# AQ-sensors-Hardware-design.net
KiCad netlist of a schematic drawn in EAGLE
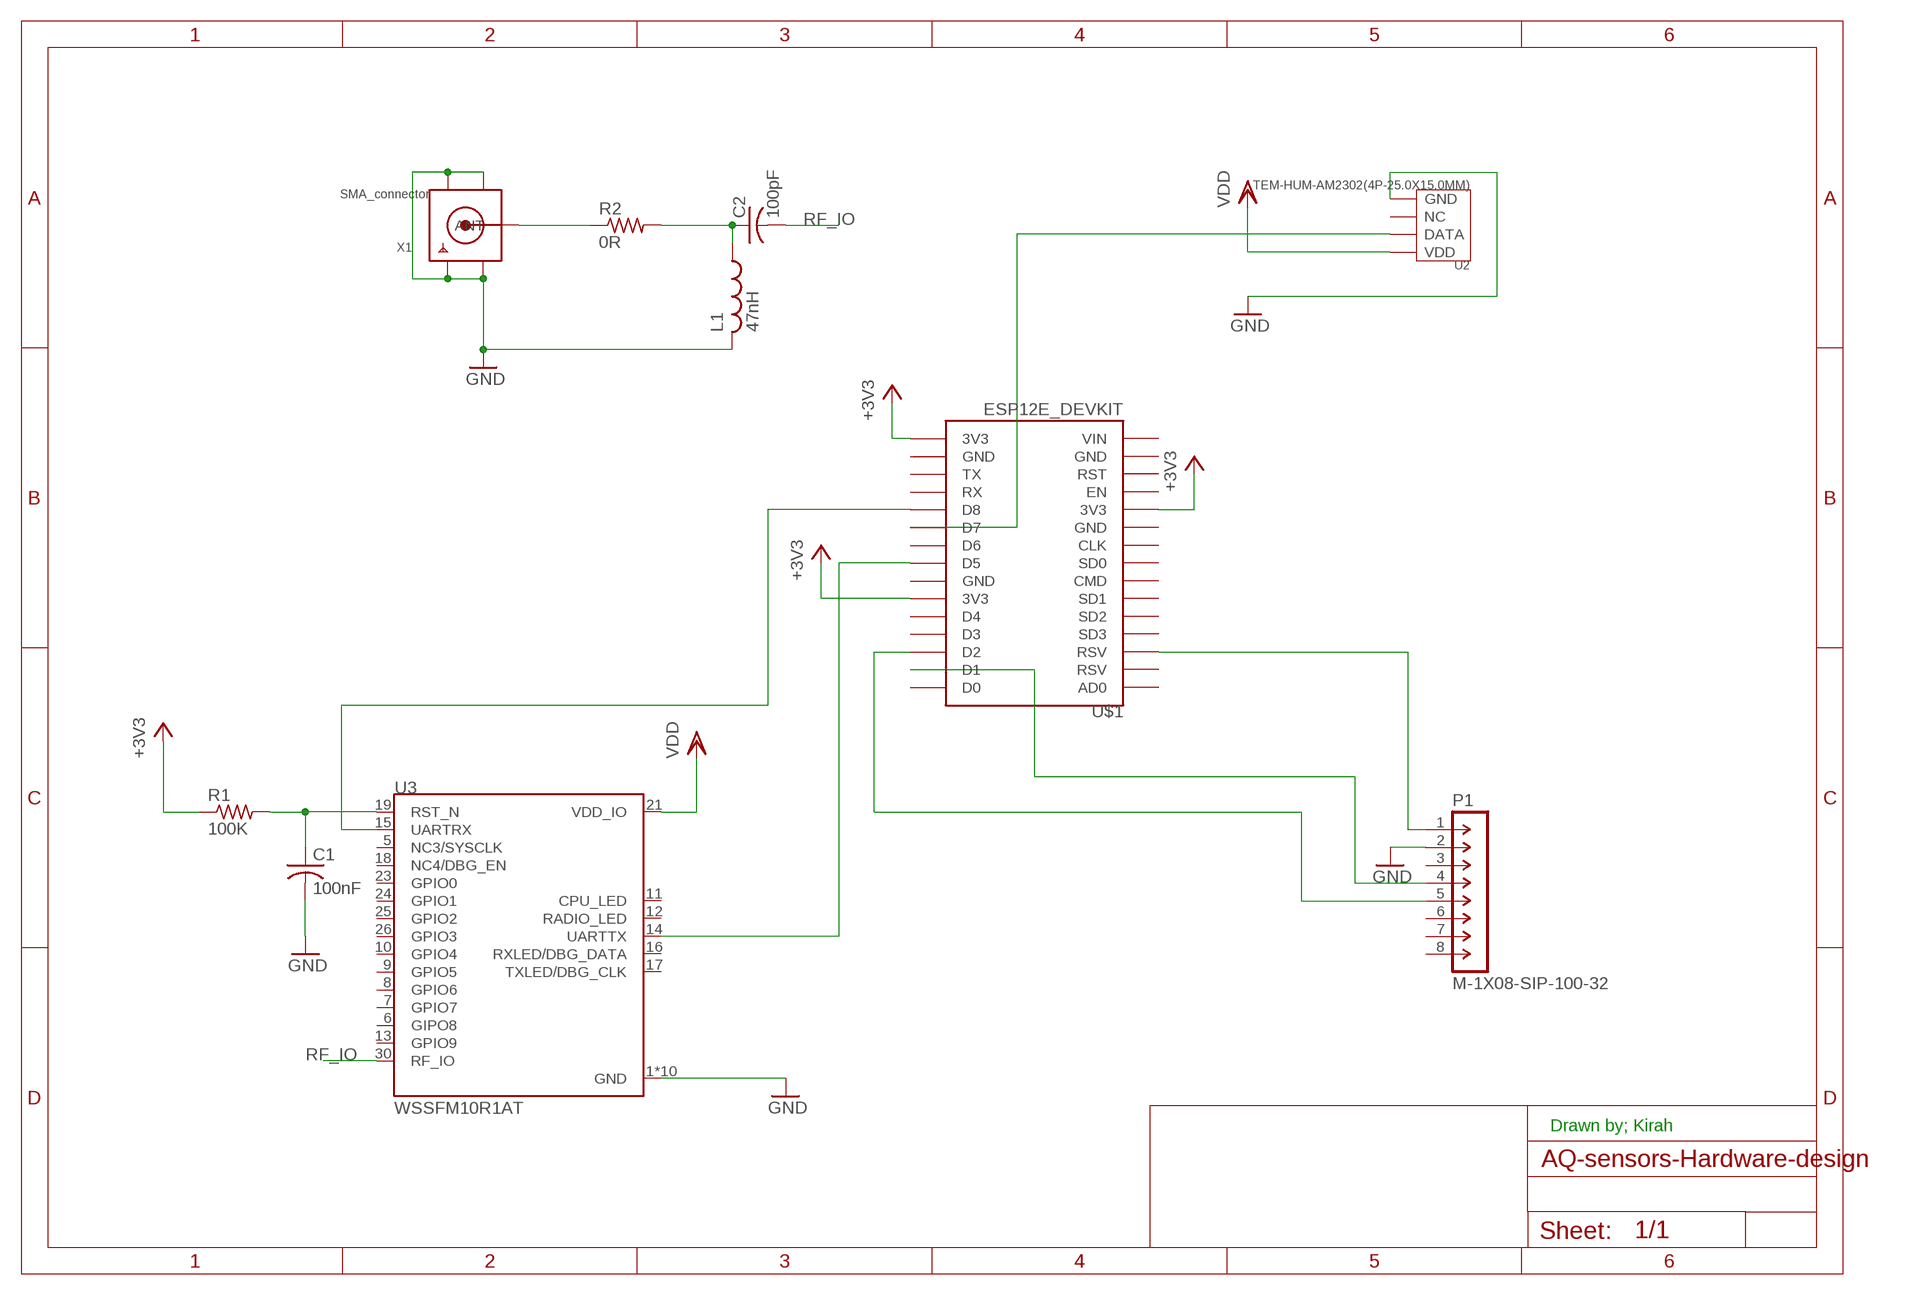
[diagram p0: schematic, sheet 1]

(export (version "E")
  (design (tool "Eeschema 10.0.6"))
  (components
    (comp (ref "C1")
      (value "100nF")
      (footprint "eagle-import:C025-025X050")
      (libsource (lib "eagle-import") (part "C-US025-025X050"))
    )
    (comp (ref "C2")
      (value "100pF")
      (footprint "eagle-import:C025-025X050")
      (libsource (lib "eagle-import") (part "C-US025-025X050"))
    )
    (comp (ref "L1")
      (value "47nH")
      (footprint "eagle-import:0204_7")
      (libsource (lib "eagle-import") (part "L-US0204/7"))
    )
    (comp (ref "P1")
      (value "M-1X08-SIP-100-32")
      (footprint "eagle-import:SIP-100-08-32")
      (libsource (lib "eagle-import") (part "M-1X08-SIP-100-32"))
    )
    (comp (ref "R1")
      (value "100K")
      (footprint "eagle-import:0204_7")
      (libsource (lib "eagle-import") (part "R-US_0204/7"))
    )
    (comp (ref "R2")
      (value "0R")
      (footprint "eagle-import:0204_7")
      (libsource (lib "eagle-import") (part "R-US_0204/7"))
    )
    (comp (ref "U$1")
      (value "ESP12E_DEVKIT")
      (footprint "eagle-import:ESP12E_DEVKIT")
      (libsource (lib "eagle-import") (part "ESP12E_DEVKIT"))
    )
    (comp (ref "U2")
      (value "TEM-HUM-AM2302(4P-25.0X15.0MM)")
      (footprint "eagle-import:SNR4-2.54-25.0X15.0X7.0MM")
      (fields (field (name "MF") "MCM Electronics") (field (name "MP") "AM2302"))
      (libsource (lib "eagle-import") (part "TEM-HUM-AM2302(4P-25.0X15.0MM)"))
    )
    (comp (ref "U3")
      (value "WSSFM10R1AT")
      (footprint "eagle-import:XCVR_WSSFM10R1AT")
      (fields (field (name "MF") "Avnet Design Services"))
      (libsource (lib "eagle-import") (part "WSSFM10R1AT"))
    )
    (comp (ref "X1")
      (value "SMA_connector")
      (footprint "eagle-import:SMA_EDGELAUNCH_UFL")
      (libsource (lib "eagle-import") (part "SMACONNECTOR_EDGE_UFL"))
    )
  )
  (nets
    (net (code "1") (name "+3V3") (class "Default")
      (node (ref "R1") (pin "1") (pinfunction "1_1") (pintype "passive"))
      (node (ref "U$1") (pin "3V3@0") (pinfunction "3V3_3V3@0") (pintype "bidirectional"))
      (node (ref "U$1") (pin "3V3@1") (pinfunction "3V3_3V3@1") (pintype "bidirectional"))
      (node (ref "U$1") (pin "3V3@2") (pinfunction "3V3_3V3@2") (pintype "bidirectional"))
    )
    (net (code "2") (name "/RF_IO") (class "Default")
      (node (ref "C2") (pin "2") (pinfunction "2_2") (pintype "passive"))
      (node (ref "U3") (pin "30") (pinfunction "RF_IO_30") (pintype "bidirectional"))
    )
    (net (code "3") (name "GND") (class "Default")
      (node (ref "C1") (pin "2") (pinfunction "2_2") (pintype "passive"))
      (node (ref "L1") (pin "2") (pinfunction "2_2") (pintype "passive"))
      (node (ref "P1") (pin "2") (pinfunction "2_2") (pintype "passive"))
      (node (ref "U2") (pin "P$4") (pinfunction "GND_P$4") (pintype "power_in"))
      (node (ref "U3") (pin "1") (pinfunction "GND_1") (pintype "power_in"))
      (node (ref "U3") (pin "2") (pinfunction "GND_2") (pintype "power_in"))
      (node (ref "U3") (pin "20") (pinfunction "GND_20") (pintype "power_in"))
      (node (ref "U3") (pin "22") (pinfunction "GND_22") (pintype "power_in"))
      (node (ref "U3") (pin "27") (pinfunction "GND_27") (pintype "power_in"))
      (node (ref "U3") (pin "28") (pinfunction "GND_28") (pintype "power_in"))
      (node (ref "U3") (pin "29") (pinfunction "GND_29") (pintype "power_in"))
      (node (ref "U3") (pin "3") (pinfunction "GND_3") (pintype "power_in"))
      (node (ref "U3") (pin "31") (pinfunction "GND_31") (pintype "power_in"))
      (node (ref "U3") (pin "4") (pinfunction "GND_4") (pintype "power_in"))
      (node (ref "X1") (pin "GND@1") (pinfunction "GND1_GND@1") (pintype "power_in"))
      (node (ref "X1") (pin "GND@2") (pinfunction "GND2_GND@2") (pintype "power_in"))
      (node (ref "X1") (pin "GND@3") (pinfunction "GND3_GND@3") (pintype "power_in"))
      (node (ref "X1") (pin "GND@4") (pinfunction "GND4_GND@4") (pintype "power_in"))
    )
    (net (code "4") (name "Net-(C2-Pad1)") (class "Default")
      (node (ref "C2") (pin "1") (pinfunction "1_1") (pintype "passive"))
      (node (ref "L1") (pin "1") (pinfunction "1_1") (pintype "passive"))
      (node (ref "R2") (pin "2") (pinfunction "2_2") (pintype "passive"))
    )
    (net (code "5") (name "Net-(P1-Pad1)") (class "Default")
      (node (ref "P1") (pin "1") (pinfunction "1_1") (pintype "passive"))
      (node (ref "U$1") (pin "RSV@1") (pinfunction "RSV_RSV@1") (pintype "bidirectional"))
    )
    (net (code "6") (name "Net-(P1-Pad4)") (class "Default")
      (node (ref "P1") (pin "4") (pinfunction "4_4") (pintype "passive"))
      (node (ref "U$1") (pin "D1") (pinfunction "D1_D1") (pintype "bidirectional"))
    )
    (net (code "7") (name "Net-(P1-Pad5)") (class "Default")
      (node (ref "P1") (pin "5") (pinfunction "5_5") (pintype "passive"))
      (node (ref "U$1") (pin "D2") (pinfunction "D2_D2") (pintype "bidirectional"))
    )
    (net (code "8") (name "Net-(U2-DATA)") (class "Default")
      (node (ref "U$1") (pin "D7") (pinfunction "D7_D7") (pintype "bidirectional"))
      (node (ref "U2") (pin "P$2") (pinfunction "DATA_P$2") (pintype "bidirectional"))
    )
    (net (code "9") (name "Net-(U3-RST_N)") (class "Default")
      (node (ref "C1") (pin "1") (pinfunction "1_1") (pintype "passive"))
      (node (ref "R1") (pin "2") (pinfunction "2_2") (pintype "passive"))
      (node (ref "U3") (pin "19") (pinfunction "RST_N_19") (pintype "input"))
    )
    (net (code "10") (name "Net-(U3-UARTRX)") (class "Default")
      (node (ref "U$1") (pin "D8") (pinfunction "D8_D8") (pintype "bidirectional"))
      (node (ref "U3") (pin "15") (pinfunction "UARTRX_15") (pintype "input"))
    )
    (net (code "11") (name "Net-(U3-UARTTX)") (class "Default")
      (node (ref "U$1") (pin "D5") (pinfunction "D5_D5") (pintype "bidirectional"))
      (node (ref "U3") (pin "14") (pinfunction "UARTTX_14") (pintype "output"))
    )
    (net (code "12") (name "Net-(X1-ANT)") (class "Default")
      (node (ref "R2") (pin "1") (pinfunction "1_1") (pintype "passive"))
      (node (ref "X1") (pin "P") (pinfunction "ANT_P") (pintype "bidirectional"))
    )
    (net (code "13") (name "VDD") (class "Default")
      (node (ref "U2") (pin "P$1") (pinfunction "VDD_P$1") (pintype "power_in"))
      (node (ref "U3") (pin "21") (pinfunction "VDD_IO_21") (pintype "power_in"))
    )
    (net (code "14") (name "unconnected-(P1-Pad3)") (class "Default")
      (node (ref "P1") (pin "3") (pinfunction "3_3") (pintype "passive"))
    )
    (net (code "15") (name "unconnected-(P1-Pad6)") (class "Default")
      (node (ref "P1") (pin "6") (pinfunction "6_6") (pintype "passive"))
    )
    (net (code "16") (name "unconnected-(P1-Pad7)") (class "Default")
      (node (ref "P1") (pin "7") (pinfunction "7_7") (pintype "passive"))
    )
    (net (code "17") (name "unconnected-(P1-Pad8)") (class "Default")
      (node (ref "P1") (pin "8") (pinfunction "8_8") (pintype "passive"))
    )
    (net (code "18") (name "unconnected-(U$1-GND-PadGND@0)") (class "Default")
      (node (ref "U$1") (pin "GND@0") (pinfunction "GND_GND@0") (pintype "bidirectional"))
    )
    (net (code "19") (name "unconnected-(U$1-GND-PadGND@1)") (class "Default")
      (node (ref "U$1") (pin "GND@1") (pinfunction "GND_GND@1") (pintype "bidirectional"))
    )
    (net (code "20") (name "unconnected-(U$1-GND-PadGND@2)") (class "Default")
      (node (ref "U$1") (pin "GND@2") (pinfunction "GND_GND@2") (pintype "bidirectional"))
    )
    (net (code "21") (name "unconnected-(U$1-GND-PadGND@3)") (class "Default")
      (node (ref "U$1") (pin "GND@3") (pinfunction "GND_GND@3") (pintype "bidirectional"))
    )
    (net (code "22") (name "unconnected-(U$1-PadAD0)") (class "Default")
      (node (ref "U$1") (pin "AD0") (pinfunction "AD0_AD0") (pintype "bidirectional"))
    )
    (net (code "23") (name "unconnected-(U$1-PadCLK)") (class "Default")
      (node (ref "U$1") (pin "CLK") (pinfunction "CLK_CLK") (pintype "bidirectional"))
    )
    (net (code "24") (name "unconnected-(U$1-PadCMD)") (class "Default")
      (node (ref "U$1") (pin "CMD") (pinfunction "CMD_CMD") (pintype "bidirectional"))
    )
    (net (code "25") (name "unconnected-(U$1-PadD0)") (class "Default")
      (node (ref "U$1") (pin "D0") (pinfunction "D0_D0") (pintype "bidirectional"))
    )
    (net (code "26") (name "unconnected-(U$1-PadD3)") (class "Default")
      (node (ref "U$1") (pin "D3") (pinfunction "D3_D3") (pintype "bidirectional"))
    )
    (net (code "27") (name "unconnected-(U$1-PadD4)") (class "Default")
      (node (ref "U$1") (pin "D4") (pinfunction "D4_D4") (pintype "bidirectional"))
    )
    (net (code "28") (name "unconnected-(U$1-PadD6)") (class "Default")
      (node (ref "U$1") (pin "D6") (pinfunction "D6_D6") (pintype "bidirectional"))
    )
    (net (code "29") (name "unconnected-(U$1-PadEN)") (class "Default")
      (node (ref "U$1") (pin "EN") (pinfunction "EN_EN") (pintype "bidirectional"))
    )
    (net (code "30") (name "unconnected-(U$1-PadRST)") (class "Default")
      (node (ref "U$1") (pin "RST") (pinfunction "RST_RST") (pintype "bidirectional"))
    )
    (net (code "31") (name "unconnected-(U$1-PadRX)") (class "Default")
      (node (ref "U$1") (pin "RX") (pinfunction "RX_RX") (pintype "bidirectional"))
    )
    (net (code "32") (name "unconnected-(U$1-PadSD0)") (class "Default")
      (node (ref "U$1") (pin "SD0") (pinfunction "SD0_SD0") (pintype "bidirectional"))
    )
    (net (code "33") (name "unconnected-(U$1-PadSD1)") (class "Default")
      (node (ref "U$1") (pin "SD1") (pinfunction "SD1_SD1") (pintype "bidirectional"))
    )
    (net (code "34") (name "unconnected-(U$1-PadSD2)") (class "Default")
      (node (ref "U$1") (pin "SD2") (pinfunction "SD2_SD2") (pintype "bidirectional"))
    )
    (net (code "35") (name "unconnected-(U$1-PadSD3)") (class "Default")
      (node (ref "U$1") (pin "SD3") (pinfunction "SD3_SD3") (pintype "bidirectional"))
    )
    (net (code "36") (name "unconnected-(U$1-PadTX)") (class "Default")
      (node (ref "U$1") (pin "TX") (pinfunction "TX_TX") (pintype "bidirectional"))
    )
    (net (code "37") (name "unconnected-(U$1-PadVIN)") (class "Default")
      (node (ref "U$1") (pin "VIN") (pinfunction "VIN_VIN") (pintype "bidirectional"))
    )
    (net (code "38") (name "unconnected-(U$1-RSV-PadRSV@0)") (class "Default")
      (node (ref "U$1") (pin "RSV@0") (pinfunction "RSV_RSV@0") (pintype "bidirectional"))
    )
    (net (code "39") (name "unconnected-(U2-NC-PadP$3)") (class "Default")
      (node (ref "U2") (pin "P$3") (pinfunction "NC_P$3") (pintype "no_connect"))
    )
    (net (code "40") (name "unconnected-(U3-CPU_LED-Pad11)") (class "Default")
      (node (ref "U3") (pin "11") (pinfunction "CPU_LED_11") (pintype "output"))
    )
    (net (code "41") (name "unconnected-(U3-GIPO8-Pad6)") (class "Default")
      (node (ref "U3") (pin "6") (pinfunction "GIPO8_6") (pintype "bidirectional"))
    )
    (net (code "42") (name "unconnected-(U3-GPIO0-Pad23)") (class "Default")
      (node (ref "U3") (pin "23") (pinfunction "GPIO0_23") (pintype "bidirectional"))
    )
    (net (code "43") (name "unconnected-(U3-GPIO1-Pad24)") (class "Default")
      (node (ref "U3") (pin "24") (pinfunction "GPIO1_24") (pintype "bidirectional"))
    )
    (net (code "44") (name "unconnected-(U3-GPIO2-Pad25)") (class "Default")
      (node (ref "U3") (pin "25") (pinfunction "GPIO2_25") (pintype "bidirectional"))
    )
    (net (code "45") (name "unconnected-(U3-GPIO3-Pad26)") (class "Default")
      (node (ref "U3") (pin "26") (pinfunction "GPIO3_26") (pintype "bidirectional"))
    )
    (net (code "46") (name "unconnected-(U3-GPIO4-Pad10)") (class "Default")
      (node (ref "U3") (pin "10") (pinfunction "GPIO4_10") (pintype "input"))
    )
    (net (code "47") (name "unconnected-(U3-GPIO5-Pad9)") (class "Default")
      (node (ref "U3") (pin "9") (pinfunction "GPIO5_9") (pintype "bidirectional"))
    )
    (net (code "48") (name "unconnected-(U3-GPIO6-Pad8)") (class "Default")
      (node (ref "U3") (pin "8") (pinfunction "GPIO6_8") (pintype "bidirectional"))
    )
    (net (code "49") (name "unconnected-(U3-GPIO7-Pad7)") (class "Default")
      (node (ref "U3") (pin "7") (pinfunction "GPIO7_7") (pintype "bidirectional"))
    )
    (net (code "50") (name "unconnected-(U3-GPIO9-Pad13)") (class "Default")
      (node (ref "U3") (pin "13") (pinfunction "GPIO9_13") (pintype "input"))
    )
    (net (code "51") (name "unconnected-(U3-NC3{slash}SYSCLK-Pad5)") (class "Default")
      (node (ref "U3") (pin "5") (pinfunction "NC3/SYSCLK_5") (pintype "input"))
    )
    (net (code "52") (name "unconnected-(U3-NC4{slash}DBG_EN-Pad18)") (class "Default")
      (node (ref "U3") (pin "18") (pinfunction "NC4/DBG_EN_18") (pintype "input"))
    )
    (net (code "53") (name "unconnected-(U3-RADIO_LED-Pad12)") (class "Default")
      (node (ref "U3") (pin "12") (pinfunction "RADIO_LED_12") (pintype "output"))
    )
    (net (code "54") (name "unconnected-(U3-RXLED{slash}DBG_DATA-Pad16)") (class "Default")
      (node (ref "U3") (pin "16") (pinfunction "RXLED/DBG_DATA_16") (pintype "output"))
    )
    (net (code "55") (name "unconnected-(U3-TXLED{slash}DBG_CLK-Pad17)") (class "Default")
      (node (ref "U3") (pin "17") (pinfunction "TXLED/DBG_CLK_17") (pintype "output"))
    )
  )
)
